# monster_dac.net
KiCad netlist of a schematic drawn in EAGLE
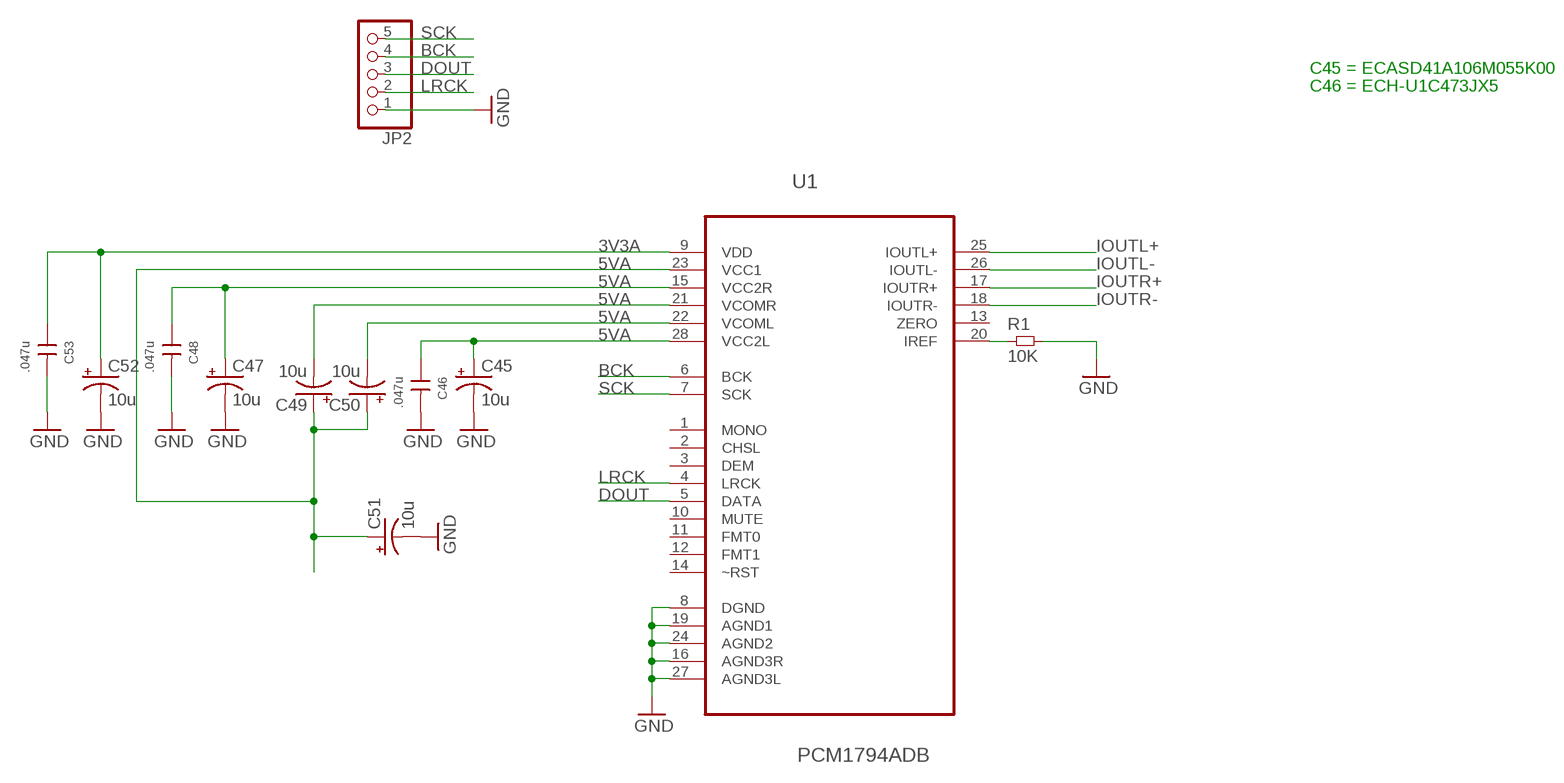
[diagram p0: schematic, sheet 1]
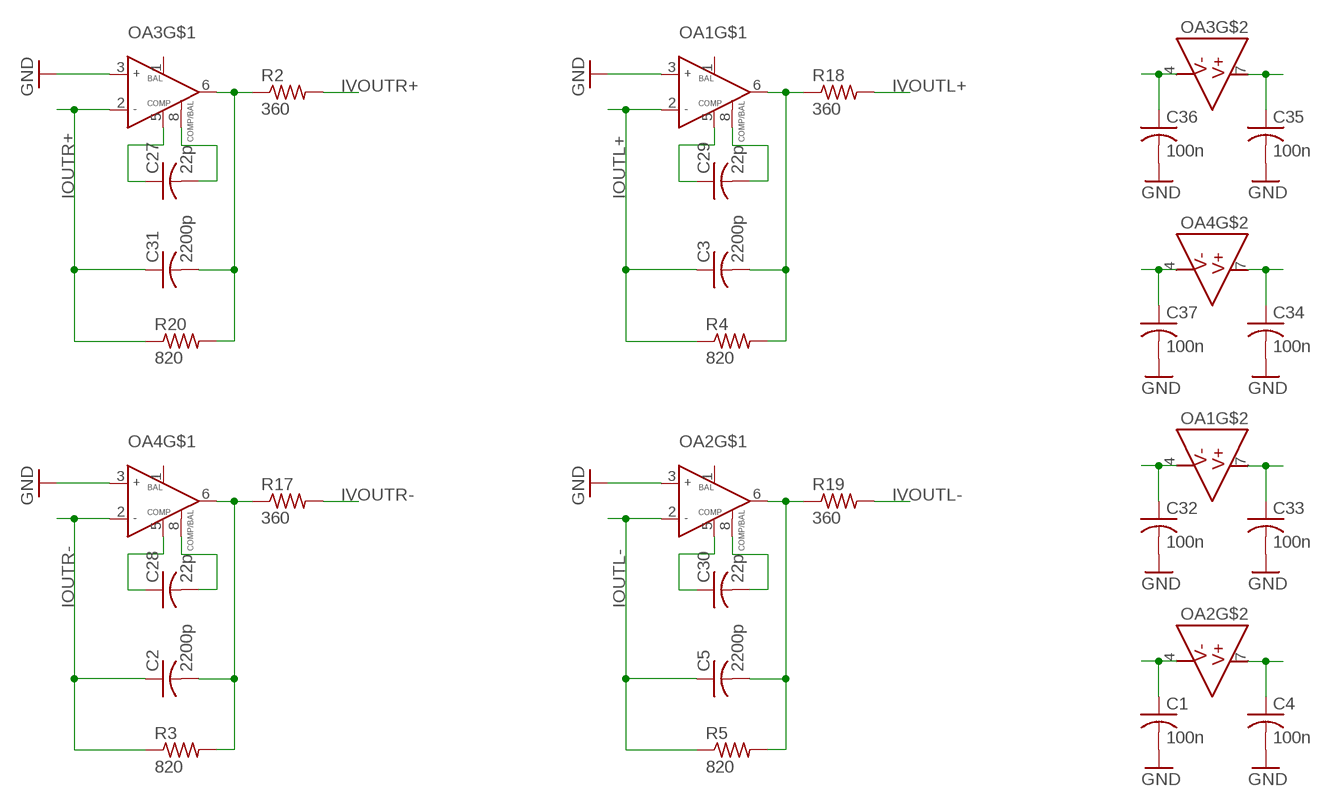
[diagram p1: schematic, sheet 2]
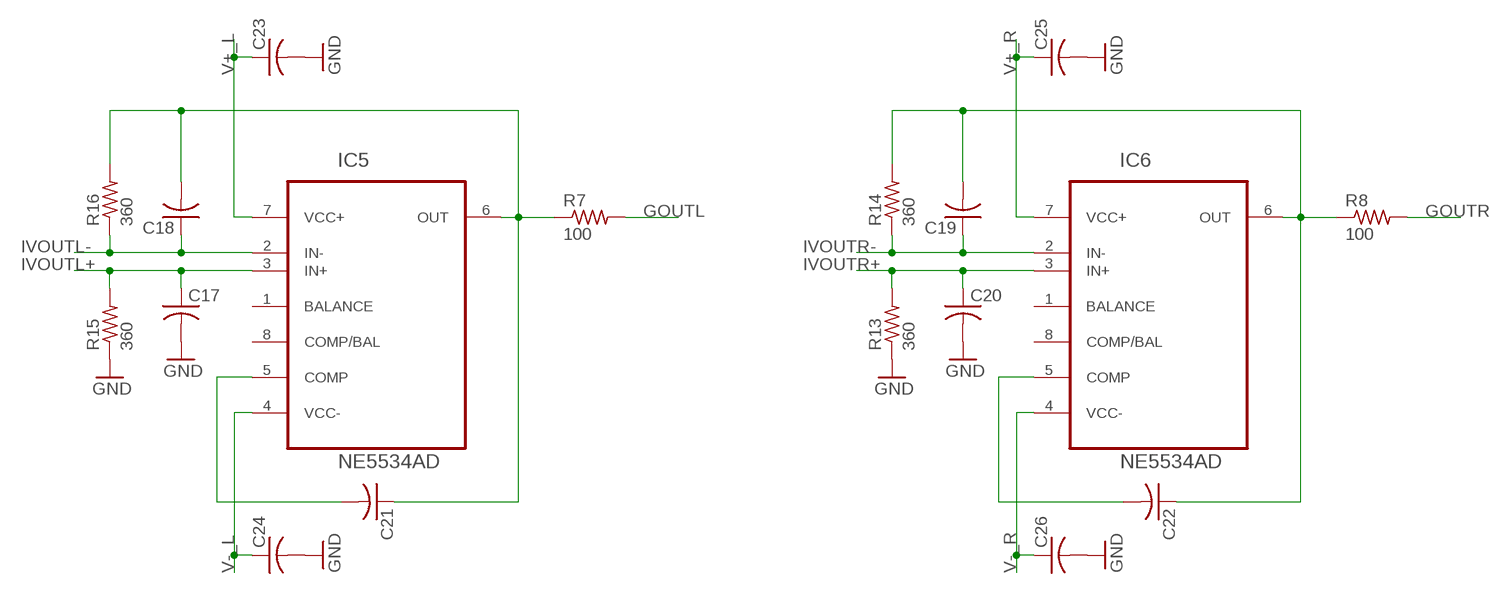
[diagram p2: schematic, sheet 3]

(export (version "E")
  (design (tool "Eeschema 10.0.6"))
  (components
    (comp (ref "C17")
      (value "C-USC0603")
      (footprint "eagle-import:C0603")
      (libsource (lib "eagle-import") (part "C-USC0603"))
    )
    (comp (ref "C18")
      (value "C-USC0603")
      (footprint "eagle-import:C0603")
      (libsource (lib "eagle-import") (part "C-USC0603"))
    )
    (comp (ref "C19")
      (value "C-USC0603")
      (footprint "eagle-import:C0603")
      (libsource (lib "eagle-import") (part "C-USC0603"))
    )
    (comp (ref "C20")
      (value "C-USC0603")
      (footprint "eagle-import:C0603")
      (libsource (lib "eagle-import") (part "C-USC0603"))
    )
    (comp (ref "C21")
      (value "C-USC0603")
      (footprint "eagle-import:C0603")
      (libsource (lib "eagle-import") (part "C-USC0603"))
    )
    (comp (ref "C22")
      (value "C-USC0603")
      (footprint "eagle-import:C0603")
      (libsource (lib "eagle-import") (part "C-USC0603"))
    )
    (comp (ref "C23")
      (value "C-USC0603")
      (footprint "eagle-import:C0603")
      (libsource (lib "eagle-import") (part "C-USC0603"))
    )
    (comp (ref "C24")
      (value "C-USC0603")
      (footprint "eagle-import:C0603")
      (libsource (lib "eagle-import") (part "C-USC0603"))
    )
    (comp (ref "C25")
      (value "C-USC0603")
      (footprint "eagle-import:C0603")
      (libsource (lib "eagle-import") (part "C-USC0603"))
    )
    (comp (ref "C26")
      (value "C-USC0603")
      (footprint "eagle-import:C0603")
      (libsource (lib "eagle-import") (part "C-USC0603"))
    )
    (comp (ref "IC5")
      (value "NE5534AD")
      (footprint "eagle-import:SOIC127P600X175-8N")
      (libsource (lib "eagle-import") (part "NE5534AD"))
    )
    (comp (ref "IC6")
      (value "NE5534AD")
      (footprint "eagle-import:SOIC127P600X175-8N")
      (libsource (lib "eagle-import") (part "NE5534AD"))
    )
    (comp (ref "R7")
      (value "100")
      (footprint "eagle-import:R0603")
      (libsource (lib "eagle-import") (part "R-US_R0603"))
    )
    (comp (ref "R8")
      (value "100")
      (footprint "eagle-import:R0603")
      (libsource (lib "eagle-import") (part "R-US_R0603"))
    )
    (comp (ref "R13")
      (value "360")
      (footprint "eagle-import:R0603")
      (libsource (lib "eagle-import") (part "R-US_R0603"))
    )
    (comp (ref "R14")
      (value "360")
      (footprint "eagle-import:R0603")
      (libsource (lib "eagle-import") (part "R-US_R0603"))
    )
    (comp (ref "R15")
      (value "360")
      (footprint "eagle-import:R0603")
      (libsource (lib "eagle-import") (part "R-US_R0603"))
    )
    (comp (ref "R16")
      (value "360")
      (footprint "eagle-import:R0603")
      (libsource (lib "eagle-import") (part "R-US_R0603"))
    )
    (comp (ref "C45")
      (value "10u")
      (footprint "eagle-import:E2-5")
      (libsource (lib "eagle-import") (part "CPOL-USE2-5"))
    )
    (comp (ref "C46")
      (value ".047u")
      (footprint "eagle-import:2,5X6,5RM5,0")
      (libsource (lib "eagle-import") (part "47NF63VMKS2"))
    )
    (comp (ref "C47")
      (value "10u")
      (footprint "eagle-import:E2-5")
      (libsource (lib "eagle-import") (part "CPOL-USE2-5"))
    )
    (comp (ref "C48")
      (value ".047u")
      (footprint "eagle-import:2,5X6,5RM5,0")
      (libsource (lib "eagle-import") (part "47NF63VMKS2"))
    )
    (comp (ref "C49")
      (value "10u")
      (footprint "eagle-import:E2-5")
      (libsource (lib "eagle-import") (part "CPOL-USE2-5"))
    )
    (comp (ref "C50")
      (value "10u")
      (footprint "eagle-import:E2-5")
      (libsource (lib "eagle-import") (part "CPOL-USE2-5"))
    )
    (comp (ref "C51")
      (value "10u")
      (footprint "eagle-import:E2-5")
      (libsource (lib "eagle-import") (part "CPOL-USE2-5"))
    )
    (comp (ref "C52")
      (value "10u")
      (footprint "eagle-import:E2-5")
      (libsource (lib "eagle-import") (part "CPOL-USE2-5"))
    )
    (comp (ref "C53")
      (value ".047u")
      (footprint "eagle-import:2,5X6,5RM5,0")
      (libsource (lib "eagle-import") (part "47NF63VMKS2"))
    )
    (comp (ref "JP2")
      (value "PINHD-1X5")
      (footprint "eagle-import:1X05")
      (libsource (lib "eagle-import") (part "PINHD-1X5"))
    )
    (comp (ref "R1")
      (value "10K")
      (footprint "eagle-import:0603L3")
      (libsource (lib "eagle-import") (part "RES0603L3"))
    )
    (comp (ref "U1")
      (value "PCM1794ADB")
      (footprint "eagle-import:SOP65P780X200-28N")
      (libsource (lib "eagle-import") (part "PCM1794ADB"))
    )
    (comp (ref "C1")
      (value "100n")
      (footprint "eagle-import:C0603")
      (libsource (lib "eagle-import") (part "C-USC0603"))
    )
    (comp (ref "C2")
      (value "2200p")
      (footprint "eagle-import:C0603")
      (libsource (lib "eagle-import") (part "C-USC0603"))
    )
    (comp (ref "C3")
      (value "2200p")
      (footprint "eagle-import:C0603")
      (libsource (lib "eagle-import") (part "C-USC0603"))
    )
    (comp (ref "C4")
      (value "100n")
      (footprint "eagle-import:C0603")
      (libsource (lib "eagle-import") (part "C-USC0603"))
    )
    (comp (ref "C5")
      (value "2200p")
      (footprint "eagle-import:C0603")
      (libsource (lib "eagle-import") (part "C-USC0603"))
    )
    (comp (ref "C27")
      (value "22p")
      (footprint "eagle-import:C0603")
      (libsource (lib "eagle-import") (part "C-USC0603"))
    )
    (comp (ref "C28")
      (value "22p")
      (footprint "eagle-import:C0603")
      (libsource (lib "eagle-import") (part "C-USC0603"))
    )
    (comp (ref "C29")
      (value "22p")
      (footprint "eagle-import:C0603")
      (libsource (lib "eagle-import") (part "C-USC0603"))
    )
    (comp (ref "C30")
      (value "22p")
      (footprint "eagle-import:C0603")
      (libsource (lib "eagle-import") (part "C-USC0603"))
    )
    (comp (ref "C31")
      (value "2200p")
      (footprint "eagle-import:C0603")
      (libsource (lib "eagle-import") (part "C-USC0603"))
    )
    (comp (ref "C32")
      (value "100n")
      (footprint "eagle-import:C0603")
      (libsource (lib "eagle-import") (part "C-USC0603"))
    )
    (comp (ref "C33")
      (value "100n")
      (footprint "eagle-import:C0603")
      (libsource (lib "eagle-import") (part "C-USC0603"))
    )
    (comp (ref "C34")
      (value "100n")
      (footprint "eagle-import:C0603")
      (libsource (lib "eagle-import") (part "C-USC0603"))
    )
    (comp (ref "C35")
      (value "100n")
      (footprint "eagle-import:C0603")
      (libsource (lib "eagle-import") (part "C-USC0603"))
    )
    (comp (ref "C36")
      (value "100n")
      (footprint "eagle-import:C0603")
      (libsource (lib "eagle-import") (part "C-USC0603"))
    )
    (comp (ref "C37")
      (value "100n")
      (footprint "eagle-import:C0603")
      (libsource (lib "eagle-import") (part "C-USC0603"))
    )
    (comp (ref "OA1")
      (value "NE5534ADSOIC8")
      (footprint "eagle-import:SOIC-8")
      (libsource (lib "eagle-import") (part "NE5534SOIC8AD"))
    )
    (comp (ref "OA2")
      (value "NE5534ADSOIC8")
      (footprint "eagle-import:SOIC-8")
      (libsource (lib "eagle-import") (part "NE5534SOIC8AD"))
    )
    (comp (ref "OA3")
      (value "NE5534ADSOIC8")
      (footprint "eagle-import:SOIC-8")
      (libsource (lib "eagle-import") (part "NE5534SOIC8AD"))
    )
    (comp (ref "OA4")
      (value "NE5534ADSOIC8")
      (footprint "eagle-import:SOIC-8")
      (libsource (lib "eagle-import") (part "NE5534SOIC8AD"))
    )
    (comp (ref "R2")
      (value "360")
      (footprint "eagle-import:R0603")
      (libsource (lib "eagle-import") (part "R-US_R0603"))
    )
    (comp (ref "R3")
      (value "820")
      (footprint "eagle-import:R0603")
      (libsource (lib "eagle-import") (part "R-US_R0603"))
    )
    (comp (ref "R4")
      (value "820")
      (footprint "eagle-import:R0603")
      (libsource (lib "eagle-import") (part "R-US_R0603"))
    )
    (comp (ref "R5")
      (value "820")
      (footprint "eagle-import:R0603")
      (libsource (lib "eagle-import") (part "R-US_R0603"))
    )
    (comp (ref "R17")
      (value "360")
      (footprint "eagle-import:R0603")
      (libsource (lib "eagle-import") (part "R-US_R0603"))
    )
    (comp (ref "R18")
      (value "360")
      (footprint "eagle-import:R0603")
      (libsource (lib "eagle-import") (part "R-US_R0603"))
    )
    (comp (ref "R19")
      (value "360")
      (footprint "eagle-import:R0603")
      (libsource (lib "eagle-import") (part "R-US_R0603"))
    )
    (comp (ref "R20")
      (value "820")
      (footprint "eagle-import:R0603")
      (libsource (lib "eagle-import") (part "R-US_R0603"))
    )
  )
  (nets
    (net (code "1") (name "3V3A") (class "Default")
      (node (ref "C52") (pin "+") (pinfunction "+_+") (pintype "passive"))
      (node (ref "C53") (pin "1") (pinfunction "1_1") (pintype "passive"))
      (node (ref "U1") (pin "9") (pinfunction "VDD_9") (pintype "power_in"))
    )
    (net (code "2") (name "5VA") (class "Default")
      (node (ref "C45") (pin "+") (pinfunction "+_+") (pintype "passive"))
      (node (ref "C46") (pin "1") (pinfunction "1_1") (pintype "passive"))
      (node (ref "C47") (pin "+") (pinfunction "+_+") (pintype "passive"))
      (node (ref "C48") (pin "1") (pinfunction "1_1") (pintype "passive"))
      (node (ref "C49") (pin "+") (pinfunction "+_+") (pintype "passive"))
      (node (ref "C49") (pin "-") (pinfunction "-_-") (pintype "passive"))
      (node (ref "C50") (pin "+") (pinfunction "+_+") (pintype "passive"))
      (node (ref "C50") (pin "-") (pinfunction "-_-") (pintype "passive"))
      (node (ref "C51") (pin "+") (pinfunction "+_+") (pintype "passive"))
      (node (ref "U1") (pin "15") (pinfunction "VCC2R_15") (pintype "power_in"))
      (node (ref "U1") (pin "21") (pinfunction "VCOMR_21") (pintype "input"))
      (node (ref "U1") (pin "22") (pinfunction "VCOML_22") (pintype "input"))
      (node (ref "U1") (pin "23") (pinfunction "VCC1_23") (pintype "power_in"))
      (node (ref "U1") (pin "28") (pinfunction "VCC2L_28") (pintype "power_in"))
    )
    (net (code "3") (name "BCK") (class "Default")
      (node (ref "JP2") (pin "4") (pinfunction "4_4") (pintype "passive"))
      (node (ref "U1") (pin "6") (pinfunction "BCK_6") (pintype "input"))
    )
    (net (code "4") (name "DOUT") (class "Default")
      (node (ref "JP2") (pin "3") (pinfunction "3_3") (pintype "passive"))
      (node (ref "U1") (pin "5") (pinfunction "DATA_5") (pintype "input"))
    )
    (net (code "5") (name "GND") (class "Default")
      (node (ref "C1") (pin "2") (pinfunction "2_2") (pintype "passive"))
      (node (ref "C17") (pin "2") (pinfunction "2_2") (pintype "passive"))
      (node (ref "C20") (pin "2") (pinfunction "2_2") (pintype "passive"))
      (node (ref "C23") (pin "2") (pinfunction "2_2") (pintype "passive"))
      (node (ref "C24") (pin "2") (pinfunction "2_2") (pintype "passive"))
      (node (ref "C25") (pin "2") (pinfunction "2_2") (pintype "passive"))
      (node (ref "C26") (pin "2") (pinfunction "2_2") (pintype "passive"))
      (node (ref "C32") (pin "2") (pinfunction "2_2") (pintype "passive"))
      (node (ref "C33") (pin "2") (pinfunction "2_2") (pintype "passive"))
      (node (ref "C34") (pin "2") (pinfunction "2_2") (pintype "passive"))
      (node (ref "C35") (pin "2") (pinfunction "2_2") (pintype "passive"))
      (node (ref "C36") (pin "2") (pinfunction "2_2") (pintype "passive"))
      (node (ref "C37") (pin "2") (pinfunction "2_2") (pintype "passive"))
      (node (ref "C4") (pin "2") (pinfunction "2_2") (pintype "passive"))
      (node (ref "C45") (pin "-") (pinfunction "-_-") (pintype "passive"))
      (node (ref "C46") (pin "2") (pinfunction "2_2") (pintype "passive"))
      (node (ref "C47") (pin "-") (pinfunction "-_-") (pintype "passive"))
      (node (ref "C48") (pin "2") (pinfunction "2_2") (pintype "passive"))
      (node (ref "C51") (pin "-") (pinfunction "-_-") (pintype "passive"))
      (node (ref "C52") (pin "-") (pinfunction "-_-") (pintype "passive"))
      (node (ref "C53") (pin "2") (pinfunction "2_2") (pintype "passive"))
      (node (ref "JP2") (pin "1") (pinfunction "1_1") (pintype "passive"))
      (node (ref "OA1") (pin "3") (pinfunction "IN+_3") (pintype "bidirectional"))
      (node (ref "OA2") (pin "3") (pinfunction "IN+_3") (pintype "bidirectional"))
      (node (ref "OA3") (pin "3") (pinfunction "IN+_3") (pintype "bidirectional"))
      (node (ref "OA4") (pin "3") (pinfunction "IN+_3") (pintype "bidirectional"))
      (node (ref "R1") (pin "P$2") (pinfunction "2_P$2") (pintype "bidirectional"))
      (node (ref "R13") (pin "1") (pinfunction "1_1") (pintype "passive"))
      (node (ref "R15") (pin "1") (pinfunction "1_1") (pintype "passive"))
      (node (ref "U1") (pin "16") (pinfunction "AGND3R_16") (pintype "passive"))
      (node (ref "U1") (pin "19") (pinfunction "AGND1_19") (pintype "passive"))
      (node (ref "U1") (pin "24") (pinfunction "AGND2_24") (pintype "passive"))
      (node (ref "U1") (pin "27") (pinfunction "AGND3L_27") (pintype "passive"))
      (node (ref "U1") (pin "8") (pinfunction "DGND_8") (pintype "passive"))
    )
    (net (code "6") (name "GOUTL") (class "Default")
      (node (ref "R7") (pin "2") (pinfunction "2_2") (pintype "passive"))
    )
    (net (code "7") (name "GOUTR") (class "Default")
      (node (ref "R8") (pin "2") (pinfunction "2_2") (pintype "passive"))
    )
    (net (code "8") (name "IOUTL+") (class "Default")
      (node (ref "C3") (pin "1") (pinfunction "1_1") (pintype "passive"))
      (node (ref "OA1") (pin "2") (pinfunction "IN-_2") (pintype "bidirectional"))
      (node (ref "R4") (pin "1") (pinfunction "1_1") (pintype "passive"))
      (node (ref "U1") (pin "25") (pinfunction "IOUTL+_25") (pintype "output"))
    )
    (net (code "9") (name "IOUTL-") (class "Default")
      (node (ref "C5") (pin "1") (pinfunction "1_1") (pintype "passive"))
      (node (ref "OA2") (pin "2") (pinfunction "IN-_2") (pintype "bidirectional"))
      (node (ref "R5") (pin "1") (pinfunction "1_1") (pintype "passive"))
      (node (ref "U1") (pin "26") (pinfunction "IOUTL-_26") (pintype "output"))
    )
    (net (code "10") (name "IOUTR+") (class "Default")
      (node (ref "C31") (pin "1") (pinfunction "1_1") (pintype "passive"))
      (node (ref "OA3") (pin "2") (pinfunction "IN-_2") (pintype "bidirectional"))
      (node (ref "R20") (pin "1") (pinfunction "1_1") (pintype "passive"))
      (node (ref "U1") (pin "17") (pinfunction "IOUTR+_17") (pintype "output"))
    )
    (net (code "11") (name "IOUTR-") (class "Default")
      (node (ref "C2") (pin "1") (pinfunction "1_1") (pintype "passive"))
      (node (ref "OA4") (pin "2") (pinfunction "IN-_2") (pintype "bidirectional"))
      (node (ref "R3") (pin "1") (pinfunction "1_1") (pintype "passive"))
      (node (ref "U1") (pin "18") (pinfunction "IOUTR-_18") (pintype "output"))
    )
    (net (code "12") (name "IVOUTL+") (class "Default")
      (node (ref "C17") (pin "1") (pinfunction "1_1") (pintype "passive"))
      (node (ref "IC5") (pin "3") (pinfunction "IN+_3") (pintype "input"))
      (node (ref "R15") (pin "2") (pinfunction "2_2") (pintype "passive"))
      (node (ref "R18") (pin "2") (pinfunction "2_2") (pintype "passive"))
    )
    (net (code "13") (name "IVOUTL-") (class "Default")
      (node (ref "C18") (pin "1") (pinfunction "1_1") (pintype "passive"))
      (node (ref "IC5") (pin "2") (pinfunction "IN-_2") (pintype "input"))
      (node (ref "R16") (pin "1") (pinfunction "1_1") (pintype "passive"))
      (node (ref "R19") (pin "2") (pinfunction "2_2") (pintype "passive"))
    )
    (net (code "14") (name "IVOUTR+") (class "Default")
      (node (ref "C20") (pin "1") (pinfunction "1_1") (pintype "passive"))
      (node (ref "IC6") (pin "3") (pinfunction "IN+_3") (pintype "input"))
      (node (ref "R13") (pin "2") (pinfunction "2_2") (pintype "passive"))
      (node (ref "R2") (pin "2") (pinfunction "2_2") (pintype "passive"))
    )
    (net (code "15") (name "IVOUTR-") (class "Default")
      (node (ref "C19") (pin "1") (pinfunction "1_1") (pintype "passive"))
      (node (ref "IC6") (pin "2") (pinfunction "IN-_2") (pintype "input"))
      (node (ref "R14") (pin "1") (pinfunction "1_1") (pintype "passive"))
      (node (ref "R17") (pin "2") (pinfunction "2_2") (pintype "passive"))
    )
    (net (code "16") (name "LRCK") (class "Default")
      (node (ref "JP2") (pin "2") (pinfunction "2_2") (pintype "passive"))
      (node (ref "U1") (pin "4") (pinfunction "LRCK_4") (pintype "input"))
    )
    (net (code "17") (name "Net-(IC5-COMP)") (class "Default")
      (node (ref "C21") (pin "2") (pinfunction "2_2") (pintype "passive"))
      (node (ref "IC5") (pin "5") (pinfunction "COMP_5") (pintype "input"))
    )
    (net (code "18") (name "Net-(IC5-OUT)") (class "Default")
      (node (ref "C18") (pin "2") (pinfunction "2_2") (pintype "passive"))
      (node (ref "C21") (pin "1") (pinfunction "1_1") (pintype "passive"))
      (node (ref "IC5") (pin "6") (pinfunction "OUT_6") (pintype "output"))
      (node (ref "R16") (pin "2") (pinfunction "2_2") (pintype "passive"))
      (node (ref "R7") (pin "1") (pinfunction "1_1") (pintype "passive"))
    )
    (net (code "19") (name "Net-(IC6-COMP)") (class "Default")
      (node (ref "C22") (pin "2") (pinfunction "2_2") (pintype "passive"))
      (node (ref "IC6") (pin "5") (pinfunction "COMP_5") (pintype "input"))
    )
    (net (code "20") (name "Net-(IC6-OUT)") (class "Default")
      (node (ref "C19") (pin "2") (pinfunction "2_2") (pintype "passive"))
      (node (ref "C22") (pin "1") (pinfunction "1_1") (pintype "passive"))
      (node (ref "IC6") (pin "6") (pinfunction "OUT_6") (pintype "output"))
      (node (ref "R14") (pin "2") (pinfunction "2_2") (pintype "passive"))
      (node (ref "R8") (pin "1") (pinfunction "1_1") (pintype "passive"))
    )
    (net (code "21") (name "Net-(OA1A-COMP)") (class "Default")
      (node (ref "C29") (pin "1") (pinfunction "1_1") (pintype "passive"))
      (node (ref "OA1") (pin "5") (pinfunction "COMP_5") (pintype "bidirectional"))
    )
    (net (code "22") (name "Net-(OA1A-COMP{slash}BAL)") (class "Default")
      (node (ref "C29") (pin "2") (pinfunction "2_2") (pintype "passive"))
      (node (ref "OA1") (pin "8") (pinfunction "COMP/BAL_8") (pintype "bidirectional"))
    )
    (net (code "23") (name "Net-(OA1A-OUT)") (class "Default")
      (node (ref "C3") (pin "2") (pinfunction "2_2") (pintype "passive"))
      (node (ref "OA1") (pin "6") (pinfunction "OUT_6") (pintype "bidirectional"))
      (node (ref "R18") (pin "1") (pinfunction "1_1") (pintype "passive"))
      (node (ref "R4") (pin "2") (pinfunction "2_2") (pintype "passive"))
    )
    (net (code "24") (name "Net-(OA1B-V+)") (class "Default")
      (node (ref "C33") (pin "1") (pinfunction "1_1") (pintype "passive"))
      (node (ref "OA1") (pin "7") (pinfunction "V+_7") (pintype "power_in"))
    )
    (net (code "25") (name "Net-(OA1B-V-)") (class "Default")
      (node (ref "C32") (pin "1") (pinfunction "1_1") (pintype "passive"))
      (node (ref "OA1") (pin "4") (pinfunction "V-_4") (pintype "power_in"))
    )
    (net (code "26") (name "Net-(OA2A-COMP)") (class "Default")
      (node (ref "C30") (pin "1") (pinfunction "1_1") (pintype "passive"))
      (node (ref "OA2") (pin "5") (pinfunction "COMP_5") (pintype "bidirectional"))
    )
    (net (code "27") (name "Net-(OA2A-COMP{slash}BAL)") (class "Default")
      (node (ref "C30") (pin "2") (pinfunction "2_2") (pintype "passive"))
      (node (ref "OA2") (pin "8") (pinfunction "COMP/BAL_8") (pintype "bidirectional"))
    )
    (net (code "28") (name "Net-(OA2A-OUT)") (class "Default")
      (node (ref "C5") (pin "2") (pinfunction "2_2") (pintype "passive"))
      (node (ref "OA2") (pin "6") (pinfunction "OUT_6") (pintype "bidirectional"))
      (node (ref "R19") (pin "1") (pinfunction "1_1") (pintype "passive"))
      (node (ref "R5") (pin "2") (pinfunction "2_2") (pintype "passive"))
    )
    (net (code "29") (name "Net-(OA2B-V+)") (class "Default")
      (node (ref "C4") (pin "1") (pinfunction "1_1") (pintype "passive"))
      (node (ref "OA2") (pin "7") (pinfunction "V+_7") (pintype "power_in"))
    )
    (net (code "30") (name "Net-(OA2B-V-)") (class "Default")
      (node (ref "C1") (pin "1") (pinfunction "1_1") (pintype "passive"))
      (node (ref "OA2") (pin "4") (pinfunction "V-_4") (pintype "power_in"))
    )
    (net (code "31") (name "Net-(OA3A-COMP)") (class "Default")
      (node (ref "C27") (pin "1") (pinfunction "1_1") (pintype "passive"))
      (node (ref "OA3") (pin "5") (pinfunction "COMP_5") (pintype "bidirectional"))
    )
    (net (code "32") (name "Net-(OA3A-COMP{slash}BAL)") (class "Default")
      (node (ref "C27") (pin "2") (pinfunction "2_2") (pintype "passive"))
      (node (ref "OA3") (pin "8") (pinfunction "COMP/BAL_8") (pintype "bidirectional"))
    )
    (net (code "33") (name "Net-(OA3A-OUT)") (class "Default")
      (node (ref "C31") (pin "2") (pinfunction "2_2") (pintype "passive"))
      (node (ref "OA3") (pin "6") (pinfunction "OUT_6") (pintype "bidirectional"))
      (node (ref "R2") (pin "1") (pinfunction "1_1") (pintype "passive"))
      (node (ref "R20") (pin "2") (pinfunction "2_2") (pintype "passive"))
    )
    (net (code "34") (name "Net-(OA3B-V+)") (class "Default")
      (node (ref "C35") (pin "1") (pinfunction "1_1") (pintype "passive"))
      (node (ref "OA3") (pin "7") (pinfunction "V+_7") (pintype "power_in"))
    )
    (net (code "35") (name "Net-(OA3B-V-)") (class "Default")
      (node (ref "C36") (pin "1") (pinfunction "1_1") (pintype "passive"))
      (node (ref "OA3") (pin "4") (pinfunction "V-_4") (pintype "power_in"))
    )
    (net (code "36") (name "Net-(OA4A-COMP)") (class "Default")
      (node (ref "C28") (pin "1") (pinfunction "1_1") (pintype "passive"))
      (node (ref "OA4") (pin "5") (pinfunction "COMP_5") (pintype "bidirectional"))
    )
    (net (code "37") (name "Net-(OA4A-COMP{slash}BAL)") (class "Default")
      (node (ref "C28") (pin "2") (pinfunction "2_2") (pintype "passive"))
      (node (ref "OA4") (pin "8") (pinfunction "COMP/BAL_8") (pintype "bidirectional"))
    )
    (net (code "38") (name "Net-(OA4A-OUT)") (class "Default")
      (node (ref "C2") (pin "2") (pinfunction "2_2") (pintype "passive"))
      (node (ref "OA4") (pin "6") (pinfunction "OUT_6") (pintype "bidirectional"))
      (node (ref "R17") (pin "1") (pinfunction "1_1") (pintype "passive"))
      (node (ref "R3") (pin "2") (pinfunction "2_2") (pintype "passive"))
    )
    (net (code "39") (name "Net-(OA4B-V+)") (class "Default")
      (node (ref "C34") (pin "1") (pinfunction "1_1") (pintype "passive"))
      (node (ref "OA4") (pin "7") (pinfunction "V+_7") (pintype "power_in"))
    )
    (net (code "40") (name "Net-(OA4B-V-)") (class "Default")
      (node (ref "C37") (pin "1") (pinfunction "1_1") (pintype "passive"))
      (node (ref "OA4") (pin "4") (pinfunction "V-_4") (pintype "power_in"))
    )
    (net (code "41") (name "Net-(R1-1)") (class "Default")
      (node (ref "R1") (pin "P$1") (pinfunction "1_P$1") (pintype "bidirectional"))
      (node (ref "U1") (pin "20") (pinfunction "IREF_20") (pintype "output"))
    )
    (net (code "42") (name "SCK") (class "Default")
      (node (ref "JP2") (pin "5") (pinfunction "5_5") (pintype "passive"))
      (node (ref "U1") (pin "7") (pinfunction "SCK_7") (pintype "input"))
    )
    (net (code "43") (name "V+_L") (class "Default")
      (node (ref "C23") (pin "1") (pinfunction "1_1") (pintype "passive"))
      (node (ref "IC5") (pin "7") (pinfunction "VCC+_7") (pintype "power_in"))
    )
    (net (code "44") (name "V+_R") (class "Default")
      (node (ref "C25") (pin "1") (pinfunction "1_1") (pintype "passive"))
      (node (ref "IC6") (pin "7") (pinfunction "VCC+_7") (pintype "power_in"))
    )
    (net (code "45") (name "V-_L") (class "Default")
      (node (ref "C24") (pin "1") (pinfunction "1_1") (pintype "passive"))
      (node (ref "IC5") (pin "4") (pinfunction "VCC-_4") (pintype "power_in"))
    )
    (net (code "46") (name "V-_R") (class "Default")
      (node (ref "C26") (pin "1") (pinfunction "1_1") (pintype "passive"))
      (node (ref "IC6") (pin "4") (pinfunction "VCC-_4") (pintype "power_in"))
    )
    (net (code "47") (name "unconnected-(IC5-BALANCE-Pad1)") (class "Default")
      (node (ref "IC5") (pin "1") (pinfunction "BALANCE_1") (pintype "input"))
    )
    (net (code "48") (name "unconnected-(IC5-COMP{slash}BAL-Pad8)") (class "Default")
      (node (ref "IC5") (pin "8") (pinfunction "COMP/BAL_8") (pintype "input"))
    )
    (net (code "49") (name "unconnected-(IC6-BALANCE-Pad1)") (class "Default")
      (node (ref "IC6") (pin "1") (pinfunction "BALANCE_1") (pintype "input"))
    )
    (net (code "50") (name "unconnected-(IC6-COMP{slash}BAL-Pad8)") (class "Default")
      (node (ref "IC6") (pin "8") (pinfunction "COMP/BAL_8") (pintype "input"))
    )
    (net (code "51") (name "unconnected-(OA1A-BAL-Pad1)") (class "Default")
      (node (ref "OA1") (pin "1") (pinfunction "BAL_1") (pintype "bidirectional"))
    )
    (net (code "52") (name "unconnected-(OA2A-BAL-Pad1)") (class "Default")
      (node (ref "OA2") (pin "1") (pinfunction "BAL_1") (pintype "bidirectional"))
    )
    (net (code "53") (name "unconnected-(OA3A-BAL-Pad1)") (class "Default")
      (node (ref "OA3") (pin "1") (pinfunction "BAL_1") (pintype "bidirectional"))
    )
    (net (code "54") (name "unconnected-(OA4A-BAL-Pad1)") (class "Default")
      (node (ref "OA4") (pin "1") (pinfunction "BAL_1") (pintype "bidirectional"))
    )
    (net (code "55") (name "unconnected-(U1-CHSL-Pad2)") (class "Default")
      (node (ref "U1") (pin "2") (pinfunction "CHSL_2") (pintype "input"))
    )
    (net (code "56") (name "unconnected-(U1-DEM-Pad3)") (class "Default")
      (node (ref "U1") (pin "3") (pinfunction "DEM_3") (pintype "input"))
    )
    (net (code "57") (name "unconnected-(U1-FMT0-Pad11)") (class "Default")
      (node (ref "U1") (pin "11") (pinfunction "FMT0_11") (pintype "input"))
    )
    (net (code "58") (name "unconnected-(U1-FMT1-Pad12)") (class "Default")
      (node (ref "U1") (pin "12") (pinfunction "FMT1_12") (pintype "input"))
    )
    (net (code "59") (name "unconnected-(U1-MONO-Pad1)") (class "Default")
      (node (ref "U1") (pin "1") (pinfunction "MONO_1") (pintype "input"))
    )
    (net (code "60") (name "unconnected-(U1-MUTE-Pad10)") (class "Default")
      (node (ref "U1") (pin "10") (pinfunction "MUTE_10") (pintype "input"))
    )
    (net (code "61") (name "unconnected-(U1-ZERO-Pad13)") (class "Default")
      (node (ref "U1") (pin "13") (pinfunction "ZERO_13") (pintype "output"))
    )
    (net (code "62") (name "unconnected-(U1-~{RST}-Pad14)") (class "Default")
      (node (ref "U1") (pin "14") (pinfunction "~{RST}_14") (pintype "input"))
    )
  )
)
